# eBox_Power.net
KiCad netlist of a schematic drawn in Altium Designer
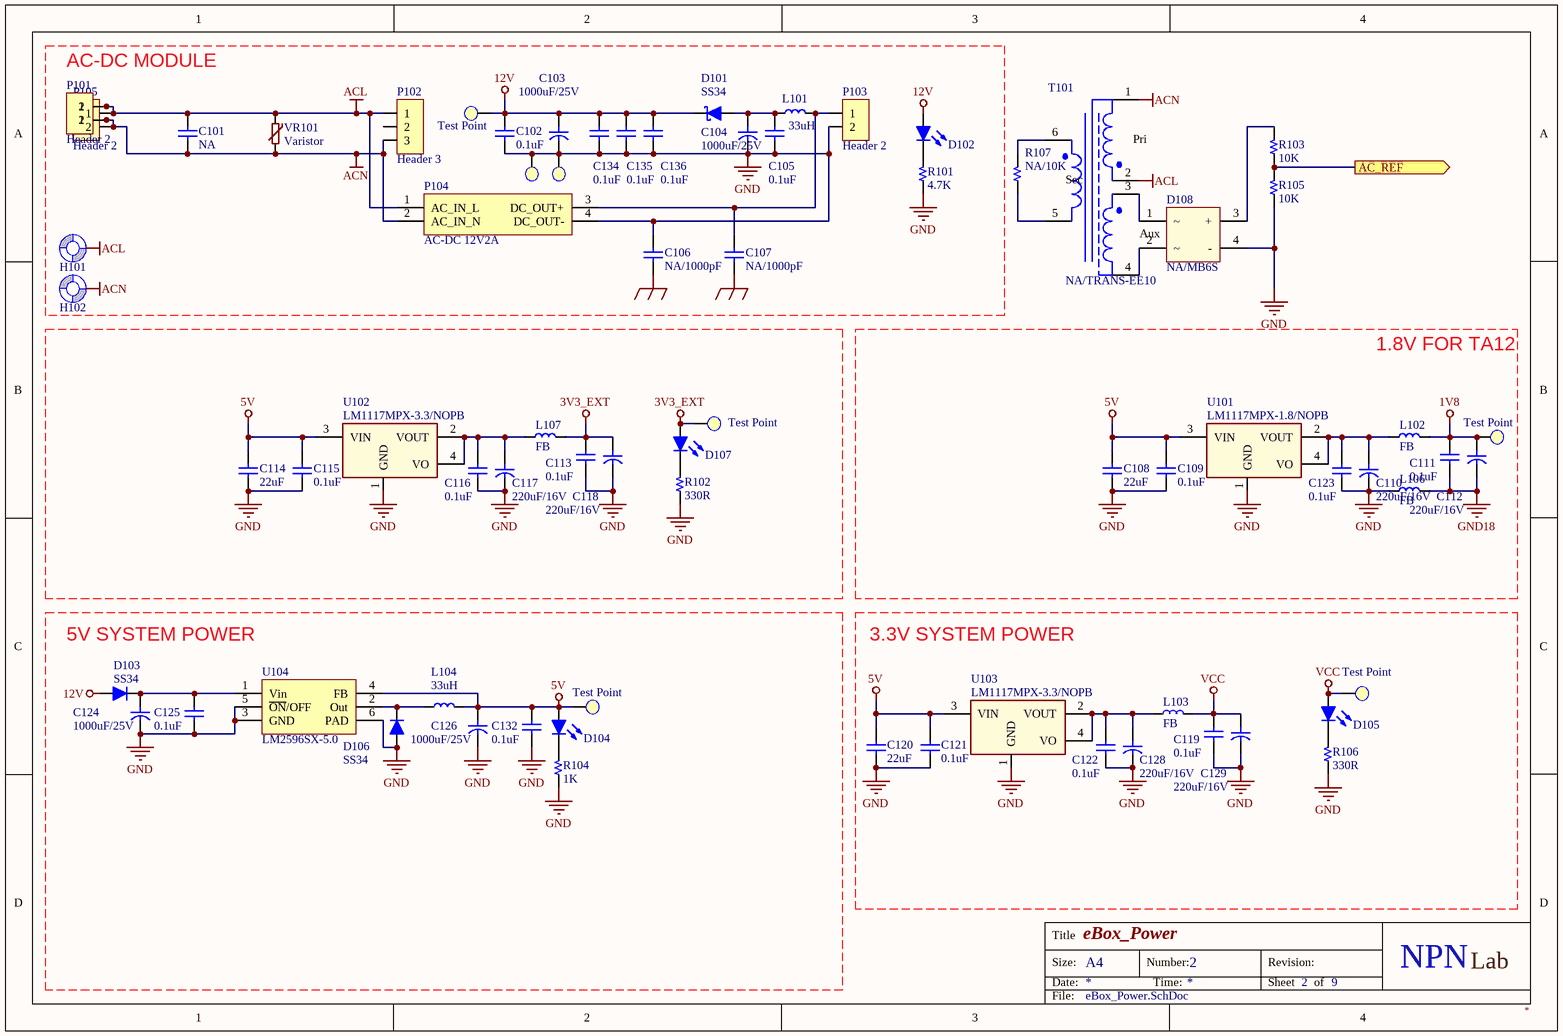
[diagram p0: eBox_Power.SchDoc]

(export (version "E")
  (design (tool "Eeschema 10.0.6"))
  (components
    (comp (ref "1V8")
      (value "Test Point")
      (footprint "TestPoint/SMD/1.5mm")
      (libsource (lib "chipfc_altium_libs_extras") (part "Test Point"))
    )
    (comp (ref "3V3EXT")
      (value "Test Point")
      (footprint "TestPoint/SMD/1.5mm")
      (libsource (lib "chipfc_altium_libs_extras") (part "Test Point"))
    )
    (comp (ref "5V")
      (value "Test Point")
      (footprint "TestPoint/SMD/1.5mm")
      (libsource (lib "chipfc_altium_libs_extras") (part "Test Point"))
    )
    (comp (ref "12V")
      (value "Test Point")
      (footprint "TestPoint/SMD/1.5mm")
      (libsource (lib "chipfc_altium_libs_extras") (part "Test Point"))
    )
    (comp (ref "C101")
      (value "NA")
      (footprint "CAP Ceramic/D7.0/F7.5")
      (description "Capacitor non-pol")
      (libsource (lib "chipfc_altium_libs") (part "Capacitor NP"))
    )
    (comp (ref "C102")
      (value "0.1uF")
      (footprint "C 0805")
      (description "CAP CER 0.1UF 50V X7R 0805")
      (libsource (lib "chipfc_altium_libs") (part "Capacitor NP"))
    )
    (comp (ref "C103")
      (value "1000uF/25V")
      (footprint "CAP/D100/H200/LS50")
      (description "CAP ALUM 1000UF 20% 25V RADIAL")
      (libsource (lib "chipfc_altium_libs") (part "Capacitor"))
    )
    (comp (ref "C104")
      (value "1000uF/25V")
      (footprint "CAP/D100/H200/LS50")
      (description "CAP ALUM 1000UF 20% 25V RADIAL")
      (libsource (lib "chipfc_altium_libs") (part "Capacitor"))
    )
    (comp (ref "C105")
      (value "0.1uF")
      (footprint "C 0805")
      (description "CAP CER 0.1UF 50V X7R 0805")
      (libsource (lib "chipfc_altium_libs") (part "Capacitor NP"))
    )
    (comp (ref "C106")
      (value "NA/1000pF")
      (footprint "CAP Ceramic/W300")
      (description "Capacitor non-pol")
      (libsource (lib "chipfc_altium_libs") (part "Capacitor NP"))
    )
    (comp (ref "C107")
      (value "NA/1000pF")
      (footprint "CAP Ceramic/W300")
      (description "Capacitor non-pol")
      (libsource (lib "chipfc_altium_libs") (part "Capacitor NP"))
    )
    (comp (ref "C108")
      (value "22uF")
      (footprint "C 1210 mix 0805")
      (description "CAP CER 22UF 10% 16V X7R 1210")
      (libsource (lib "chipfc_altium_libs") (part "Capacitor NP"))
    )
    (comp (ref "C109")
      (value "0.1uF")
      (footprint "C 0805")
      (description "CAP CER 0.1UF 50V X7R 0805")
      (libsource (lib "chipfc_altium_libs") (part "Capacitor NP"))
    )
    (comp (ref "C110")
      (value "220uF/16V")
      (footprint "CYL/D.250/LS.100-D63H70P25")
      (description "CAP ALUM 220UF 20% 16V RADIAL")
      (libsource (lib "") (part "Capacitor_1"))
    )
    (comp (ref "C111")
      (value "0.1uF")
      (footprint "C 0805")
      (description "CAP CER 0.1UF 50V X7R 0805")
      (libsource (lib "chipfc_altium_libs") (part "Capacitor NP"))
    )
    (comp (ref "C112")
      (value "220uF/16V")
      (footprint "CYL/D.250/LS.100-D63H70P25")
      (description "CAP ALUM 220UF 20% 16V RADIAL")
      (libsource (lib "") (part "Capacitor_1"))
    )
    (comp (ref "C113")
      (value "0.1uF")
      (footprint "C 0805")
      (description "CAP CER 0.1UF 50V X7R 0805")
      (libsource (lib "chipfc_altium_libs") (part "Capacitor NP"))
    )
    (comp (ref "C114")
      (value "22uF")
      (footprint "C 1210 mix 0805")
      (description "CAP CER 22UF 10% 16V X7R 1210")
      (libsource (lib "chipfc_altium_libs") (part "Capacitor NP"))
    )
    (comp (ref "C115")
      (value "0.1uF")
      (footprint "C 0805")
      (description "CAP CER 0.1UF 50V X7R 0805")
      (libsource (lib "chipfc_altium_libs") (part "Capacitor NP"))
    )
    (comp (ref "C116")
      (value "0.1uF")
      (footprint "C 0805")
      (description "CAP CER 0.1UF 50V X7R 0805")
      (libsource (lib "chipfc_altium_libs") (part "Capacitor NP"))
    )
    (comp (ref "C117")
      (value "220uF/16V")
      (footprint "CYL/D.250/LS.100-D63H70P25")
      (description "CAP ALUM 220UF 20% 16V RADIAL")
      (libsource (lib "") (part "Capacitor_1"))
    )
    (comp (ref "C118")
      (value "220uF/16V")
      (footprint "CYL/D.250/LS.100-D63H70P25")
      (description "CAP ALUM 220UF 20% 16V RADIAL")
      (libsource (lib "") (part "Capacitor_1"))
    )
    (comp (ref "C119")
      (value "0.1uF")
      (footprint "C 0805")
      (description "CAP CER 0.1UF 50V X7R 0805")
      (libsource (lib "chipfc_altium_libs") (part "Capacitor NP"))
    )
    (comp (ref "C120")
      (value "22uF")
      (footprint "C 1210 mix 0805")
      (description "CAP CER 22UF 10% 16V X7R 1210")
      (libsource (lib "chipfc_altium_libs") (part "Capacitor NP"))
    )
    (comp (ref "C121")
      (value "0.1uF")
      (footprint "C 0805")
      (description "CAP CER 0.1UF 50V X7R 0805")
      (libsource (lib "chipfc_altium_libs") (part "Capacitor NP"))
    )
    (comp (ref "C122")
      (value "0.1uF")
      (footprint "C 0805")
      (description "CAP CER 0.1UF 50V X7R 0805")
      (libsource (lib "chipfc_altium_libs") (part "Capacitor NP"))
    )
    (comp (ref "C123")
      (value "0.1uF")
      (footprint "C 0805")
      (description "CAP CER 0.1UF 50V X7R 0805")
      (libsource (lib "chipfc_altium_libs") (part "Capacitor NP"))
    )
    (comp (ref "C124")
      (value "1000uF/25V")
      (footprint "CAP/D100/H200/LS50")
      (description "CAP ALUM 1000UF 20% 25V RADIAL")
      (libsource (lib "chipfc_altium_libs") (part "Capacitor"))
    )
    (comp (ref "C125")
      (value "0.1uF")
      (footprint "C 0805")
      (description "CAP CER 0.1UF 50V X7R 0805")
      (libsource (lib "chipfc_altium_libs") (part "Capacitor NP"))
    )
    (comp (ref "C126")
      (value "1000uF/25V")
      (footprint "CAP/D100/H200/LS50")
      (description "CAP ALUM 1000UF 20% 25V RADIAL")
      (libsource (lib "chipfc_altium_libs") (part "Capacitor"))
    )
    (comp (ref "C128")
      (value "220uF/16V")
      (footprint "CYL/D.250/LS.100-D63H70P25")
      (description "CAP ALUM 220UF 20% 16V RADIAL")
      (libsource (lib "") (part "Capacitor_1"))
    )
    (comp (ref "C129")
      (value "220uF/16V")
      (footprint "CYL/D.250/LS.100-D63H70P25")
      (description "CAP ALUM 220UF 20% 16V RADIAL")
      (libsource (lib "") (part "Capacitor_1"))
    )
    (comp (ref "C132")
      (value "0.1uF")
      (footprint "C 0805")
      (description "CAP CER 0.1UF 50V X7R 0805")
      (libsource (lib "chipfc_altium_libs") (part "Capacitor NP"))
    )
    (comp (ref "C134")
      (value "0.1uF")
      (footprint "C 0805")
      (description "CAP CER 0.1UF 50V X7R 0805")
      (libsource (lib "chipfc_altium_libs") (part "Capacitor NP"))
    )
    (comp (ref "C135")
      (value "0.1uF")
      (footprint "C 0805")
      (description "CAP CER 0.1UF 50V X7R 0805")
      (libsource (lib "chipfc_altium_libs") (part "Capacitor NP"))
    )
    (comp (ref "C136")
      (value "0.1uF")
      (footprint "C 0805")
      (description "CAP CER 0.1UF 50V X7R 0805")
      (libsource (lib "chipfc_altium_libs") (part "Capacitor NP"))
    )
    (comp (ref "D101")
      (value "SS34")
      (footprint "DO-214AB (SMC)")
      (description "DIODE SCHOTTKY 40V 3A SUB SMA")
      (libsource (lib "chipfc_altium_libs") (part "Diode Schottky"))
    )
    (comp (ref "D102")
      (value "LED RED 3MM")
      (footprint "LED 3MM - red")
      (description "LED RED DIFFUSED 3MM ROUND T/H")
      (libsource (lib "chipfc_altium_libs") (part "Led"))
    )
    (comp (ref "D103")
      (value "SS34")
      (footprint "DO-214AC (SMA) L")
      (description "DIODE SCHOTTKY 40V 3A SUB SMA")
      (libsource (lib "chipfc_altium_libs") (part "Diode"))
    )
    (comp (ref "D104")
      (value "LED RED 3MM")
      (footprint "LED 3MM - red")
      (description "LED RED DIFFUSED 3MM ROUND T/H")
      (libsource (lib "chipfc_altium_libs") (part "Led"))
    )
    (comp (ref "D105")
      (value "LED RED 3MM")
      (footprint "LED 3MM - red")
      (description "LED RED DIFFUSED 3MM ROUND T/H")
      (libsource (lib "chipfc_altium_libs") (part "Led"))
    )
    (comp (ref "D106")
      (value "SS34")
      (footprint "DO-214AC (SMA) L")
      (description "DIODE SCHOTTKY 40V 3A SUB SMA")
      (libsource (lib "chipfc_altium_libs") (part "Diode"))
    )
    (comp (ref "D107")
      (value "LED RED 3MM")
      (footprint "LED 3MM - red")
      (description "LED RED DIFFUSED 3MM ROUND T/H")
      (libsource (lib "chipfc_altium_libs") (part "Led"))
    )
    (comp (ref "D108")
      (value "NA/MB6S")
      (footprint "DiodeBridge-SOIC4")
      (description "BRIDGE RECT 1P 600V 500MA 4SOIC")
      (fields (field (name "PART NO") "MB6S"))
      (libsource (lib "chipfc_altium_libs") (part "DIODE BRIDGE"))
    )
    (comp (ref "GND2")
      (value "Test Point")
      (footprint "TESTPOINT/1/Black")
      (libsource (lib "chipfc_altium_libs_extras") (part "Test Point"))
    )
    (comp (ref "GND3")
      (value "Test Point")
      (footprint "TESTPOINT/1/Black")
      (libsource (lib "chipfc_altium_libs_extras") (part "Test Point"))
    )
    (comp (ref "H101")
      (value "Screw Hole")
      (footprint "SCREW/3.0/6.0")
      (libsource (lib "chipfc_altium_libs") (part "Screw Hole"))
    )
    (comp (ref "H102")
      (value "Screw Hole")
      (footprint "SCREW/3.0/6.0")
      (libsource (lib "chipfc_altium_libs") (part "Screw Hole"))
    )
    (comp (ref "L101")
      (value "33uH")
      (footprint "Inductor SMD 6.5x6.5x3.0")
      (description "FIXED IND 33UH 3A 105 MOHM SMD")
      (libsource (lib "chipfc_altium_libs") (part "Inductor"))
    )
    (comp (ref "L102")
      (value "FB")
      (footprint "L 0805 (2012)")
      (description "Chip Ferrite Bead")
      (libsource (lib "chipfc_altium_libs") (part "Inductor"))
    )
    (comp (ref "L103")
      (value "FB")
      (footprint "L 0805 (2012)")
      (description "Chip Ferrite Bead")
      (libsource (lib "chipfc_altium_libs") (part "Inductor"))
    )
    (comp (ref "L104")
      (value "33uH")
      (footprint "Inductor SMD 12x12x8")
      (description "FIXED IND 33UH 3A 64.8 MOHM SMD")
      (libsource (lib "chipfc_altium_libs") (part "Inductor"))
    )
    (comp (ref "L105")
      (value "33uH")
      (footprint "Inductor SMD 12x12x8")
      (description "FIXED IND 33UH 3A 64.8 MOHM SMD")
      (libsource (lib "chipfc_altium_libs") (part "Inductor"))
    )
    (comp (ref "L106")
      (value "FB")
      (footprint "L 0805 (2012)")
      (description "Chip Ferrite Bead")
      (libsource (lib "chipfc_altium_libs") (part "Inductor"))
    )
    (comp (ref "L107")
      (value "FB")
      (footprint "L 0805 (2012)")
      (description "Chip Ferrite Bead")
      (libsource (lib "chipfc_altium_libs") (part "Inductor"))
    )
    (comp (ref "P101")
      (value "Header 2")
      (footprint "HDR/Terminal/2/KF55C-10")
      (description "Header, 2-Pin")
      (libsource (lib "") (part "Header 2_1"))
    )
    (comp (ref "P102")
      (value "Header 3")
      (footprint "HDR/Header/3/VH")
      (description "Header, 3-Pin")
      (libsource (lib "chipfc_altium_libs") (part "Header 3"))
    )
    (comp (ref "P103")
      (value "Header 2")
      (footprint "HDR/Header/2/VH")
      (description "Header, 2-Pin")
      (libsource (lib "chipfc_altium_libs") (part "Header 2"))
    )
    (comp (ref "P104")
      (value "AC-DC 12V2A")
      (footprint "AC-DC 12V2A")
      (description "AC-DC 12V2A MODULE")
      (libsource (lib "chipfc_altium_libs") (part "AC-DC 12V3A"))
    )
    (comp (ref "P105")
      (value "Header 2")
      (footprint "HDR/Terminal/2/KF1000")
      (description "Header, 2-Pin")
      (libsource (lib "") (part "Header 2_1"))
    )
    (comp (ref "P106")
      (value "Header 2")
      (footprint "HDR/Terminal/2/KF1000")
      (description "Header, 2-Pin")
      (libsource (lib "") (part "Header 2_2"))
    )
    (comp (ref "R101")
      (value "4.7K")
      (footprint "R 0603")
      (description "RES SMD 4.7K OHM 1% 1/10W 0603")
      (libsource (lib "chipfc_altium_libs") (part "Resistor"))
    )
    (comp (ref "R102")
      (value "330R")
      (footprint "R 0603")
      (description "RES SMD 330 OHM 1% 1/10W 0603")
      (libsource (lib "chipfc_altium_libs") (part "Resistor"))
    )
    (comp (ref "R103")
      (value "10K")
      (footprint "R 0805")
      (description "RES SMD 10K OHM 1% 1/8W 0805")
      (libsource (lib "chipfc_altium_libs") (part "Resistor"))
    )
    (comp (ref "R104")
      (value "1K")
      (footprint "R 0603")
      (description "RES SMD 1K OHM 1% 1/10W 0603")
      (libsource (lib "chipfc_altium_libs") (part "Resistor"))
    )
    (comp (ref "R105")
      (value "10K")
      (footprint "R 0805")
      (description "RES SMD 10K OHM 1% 1/8W 0805")
      (libsource (lib "chipfc_altium_libs") (part "Resistor"))
    )
    (comp (ref "R106")
      (value "330R")
      (footprint "R 0603")
      (description "RES SMD 330 OHM 1% 1/10W 0603")
      (libsource (lib "chipfc_altium_libs") (part "Resistor"))
    )
    (comp (ref "R107")
      (value "NA/10K")
      (footprint "R 0805")
      (description "RES SMD 10K OHM 5% 1/8W 0805")
      (libsource (lib "chipfc_altium_libs") (part "Resistor"))
    )
    (comp (ref "T101")
      (value "NA/TRANS-EE10")
      (footprint "Trans. EE10/6P/F")
      (description "Transformer 6-PIN")
      (libsource (lib "chipfc_altium_libs") (part "Trans 6-PIN"))
    )
    (comp (ref "U101")
      (value "LM1117MPX-1.8/NOPB")
      (footprint "SOT-223")
      (description "IC REG LINEAR 1.8V 800MA SOT223")
      (libsource (lib "chipfc_altium_libs") (part "AMS1117"))
    )
    (comp (ref "U102")
      (value "LM1117MPX-3.3/NOPB")
      (footprint "SOT-223")
      (description "IC REG LINEAR 3.3V 800MA SOT223")
      (libsource (lib "chipfc_altium_libs") (part "AMS1117"))
    )
    (comp (ref "U103")
      (value "LM1117MPX-3.3/NOPB")
      (footprint "SOT-223")
      (description "IC REG LINEAR 3.3V 800MA SOT223")
      (libsource (lib "chipfc_altium_libs") (part "AMS1117"))
    )
    (comp (ref "U104")
      (value "LM2596SX-5.0")
      (footprint "TO-263-6")
      (description "IC REG BUCK 5V 3A TO263-5")
      (fields (field (name "PART NO") "LM2576SX-5.0/NOPB"))
      (libsource (lib "chipfc_altium_libs") (part "LM2576SX-5.0"))
    )
    (comp (ref "VCC")
      (value "Test Point")
      (footprint "TestPoint/SMD/1.5mm")
      (libsource (lib "chipfc_altium_libs_extras") (part "Test Point"))
    )
    (comp (ref "VR101")
      (value "Varistor")
      (footprint "VARISTOR DISC 5MM/7MM")
      (libsource (lib "chipfc_altium_libs") (part "Varistor"))
    )
  )
  (nets
    (net (code "1") (name "/AC_REF") (class "Default")
      (node (ref "R103") (pin "1") (pinfunction "1_1") (pintype "passive"))
      (node (ref "R105") (pin "2") (pinfunction "2_2") (pintype "passive"))
    )
    (net (code "2") (name "1V8") (class "Default")
      (node (ref "1V8") (pin "1") (pinfunction "TP_1") (pintype "passive"))
      (node (ref "C111") (pin "1") (pinfunction "1_1") (pintype "passive"))
      (node (ref "C112") (pin "1") (pinfunction "1_1") (pintype "passive"))
      (node (ref "L102") (pin "2") (pinfunction "2_2") (pintype "passive"))
    )
    (net (code "3") (name "3V3_EXT") (class "Default")
      (node (ref "3V3EXT") (pin "1") (pinfunction "TP_1") (pintype "passive"))
      (node (ref "C113") (pin "1") (pinfunction "1_1") (pintype "passive"))
      (node (ref "C118") (pin "1") (pinfunction "1_1") (pintype "passive"))
      (node (ref "D107") (pin "1") (pinfunction "A_1") (pintype "passive"))
      (node (ref "L107") (pin "2") (pinfunction "2_2") (pintype "passive"))
    )
    (net (code "4") (name "5V") (class "Default")
      (node (ref "5V") (pin "1") (pinfunction "TP_1") (pintype "passive"))
      (node (ref "C108") (pin "1") (pinfunction "1_1") (pintype "passive"))
      (node (ref "C109") (pin "1") (pinfunction "1_1") (pintype "passive"))
      (node (ref "C114") (pin "1") (pinfunction "1_1") (pintype "passive"))
      (node (ref "C115") (pin "1") (pinfunction "1_1") (pintype "passive"))
      (node (ref "C120") (pin "1") (pinfunction "1_1") (pintype "passive"))
      (node (ref "C121") (pin "1") (pinfunction "1_1") (pintype "passive"))
      (node (ref "C126") (pin "1") (pinfunction "1_1") (pintype "passive"))
      (node (ref "C132") (pin "1") (pinfunction "1_1") (pintype "passive"))
      (node (ref "D104") (pin "1") (pinfunction "A_1") (pintype "passive"))
      (node (ref "L104") (pin "2") (pinfunction "2_2") (pintype "passive"))
      (node (ref "U101") (pin "3") (pinfunction "VIN_3") (pintype "power_in"))
      (node (ref "U102") (pin "3") (pinfunction "VIN_3") (pintype "power_in"))
      (node (ref "U103") (pin "3") (pinfunction "VIN_3") (pintype "power_in"))
      (node (ref "U104") (pin "4") (pinfunction "FB_4") (pintype "passive"))
    )
    (net (code "5") (name "12V") (class "Default")
      (node (ref "12V") (pin "1") (pinfunction "TP_1") (pintype "passive"))
      (node (ref "C102") (pin "1") (pinfunction "1_1") (pintype "passive"))
      (node (ref "C103") (pin "1") (pinfunction "1_1") (pintype "passive"))
      (node (ref "C134") (pin "1") (pinfunction "1_1") (pintype "passive"))
      (node (ref "C135") (pin "1") (pinfunction "1_1") (pintype "passive"))
      (node (ref "C136") (pin "1") (pinfunction "1_1") (pintype "passive"))
      (node (ref "D101") (pin "2") (pinfunction "K_2") (pintype "passive"))
      (node (ref "D102") (pin "1") (pinfunction "A_1") (pintype "passive"))
      (node (ref "D103") (pin "1") (pinfunction "A_1") (pintype "passive"))
    )
    (net (code "6") (name "ACL") (class "Default")
      (node (ref "C101") (pin "1") (pinfunction "1_1") (pintype "passive"))
      (node (ref "H101") (pin "1") (pinfunction "Screw_1") (pintype "passive"))
      (node (ref "P101") (pin "1") (pinfunction "1_1") (pintype "passive"))
      (node (ref "P102") (pin "1") (pinfunction "1_1") (pintype "passive"))
      (node (ref "P104") (pin "1") (pinfunction "AC_IN_L_1") (pintype "passive"))
      (node (ref "P105") (pin "1") (pinfunction "1_1") (pintype "passive"))
      (node (ref "P106") (pin "2") (pinfunction "2_2") (pintype "passive"))
      (node (ref "T101") (pin "2") (pinfunction "A2_2") (pintype "passive"))
      (node (ref "VR101") (pin "2") (pinfunction "2_2") (pintype "passive"))
    )
    (net (code "7") (name "ACN") (class "Default")
      (node (ref "C101") (pin "2") (pinfunction "2_2") (pintype "passive"))
      (node (ref "H102") (pin "1") (pinfunction "Screw_1") (pintype "passive"))
      (node (ref "P101") (pin "2") (pinfunction "2_2") (pintype "passive"))
      (node (ref "P102") (pin "3") (pinfunction "3_3") (pintype "passive"))
      (node (ref "P104") (pin "2") (pinfunction "AC_IN_N_2") (pintype "passive"))
      (node (ref "P105") (pin "2") (pinfunction "2_2") (pintype "passive"))
      (node (ref "P106") (pin "1") (pinfunction "1_1") (pintype "passive"))
      (node (ref "T101") (pin "1") (pinfunction "A1_1") (pintype "passive"))
      (node (ref "VR101") (pin "1") (pinfunction "1_1") (pintype "passive"))
    )
    (net (code "8") (name "GND") (class "Default")
      (node (ref "C102") (pin "2") (pinfunction "2_2") (pintype "passive"))
      (node (ref "C103") (pin "2") (pinfunction "2_2") (pintype "passive"))
      (node (ref "C104") (pin "2") (pinfunction "2_2") (pintype "passive"))
      (node (ref "C105") (pin "2") (pinfunction "2_2") (pintype "passive"))
      (node (ref "C106") (pin "1") (pinfunction "1_1") (pintype "passive"))
      (node (ref "C108") (pin "2") (pinfunction "2_2") (pintype "passive"))
      (node (ref "C109") (pin "2") (pinfunction "2_2") (pintype "passive"))
      (node (ref "C110") (pin "2") (pinfunction "2_2") (pintype "passive"))
      (node (ref "C113") (pin "2") (pinfunction "2_2") (pintype "passive"))
      (node (ref "C114") (pin "2") (pinfunction "2_2") (pintype "passive"))
      (node (ref "C115") (pin "2") (pinfunction "2_2") (pintype "passive"))
      (node (ref "C116") (pin "2") (pinfunction "2_2") (pintype "passive"))
      (node (ref "C117") (pin "2") (pinfunction "2_2") (pintype "passive"))
      (node (ref "C118") (pin "2") (pinfunction "2_2") (pintype "passive"))
      (node (ref "C119") (pin "2") (pinfunction "2_2") (pintype "passive"))
      (node (ref "C120") (pin "2") (pinfunction "2_2") (pintype "passive"))
      (node (ref "C121") (pin "2") (pinfunction "2_2") (pintype "passive"))
      (node (ref "C122") (pin "2") (pinfunction "2_2") (pintype "passive"))
      (node (ref "C123") (pin "2") (pinfunction "2_2") (pintype "passive"))
      (node (ref "C124") (pin "2") (pinfunction "2_2") (pintype "passive"))
      (node (ref "C125") (pin "2") (pinfunction "2_2") (pintype "passive"))
      (node (ref "C126") (pin "2") (pinfunction "2_2") (pintype "passive"))
      (node (ref "C128") (pin "2") (pinfunction "2_2") (pintype "passive"))
      (node (ref "C129") (pin "2") (pinfunction "2_2") (pintype "passive"))
      (node (ref "C132") (pin "2") (pinfunction "2_2") (pintype "passive"))
      (node (ref "C134") (pin "2") (pinfunction "2_2") (pintype "passive"))
      (node (ref "C135") (pin "2") (pinfunction "2_2") (pintype "passive"))
      (node (ref "C136") (pin "2") (pinfunction "2_2") (pintype "passive"))
      (node (ref "D106") (pin "1") (pinfunction "A_1") (pintype "passive"))
      (node (ref "D108") (pin "4") (pinfunction "-_4") (pintype "passive"))
      (node (ref "GND2") (pin "1") (pinfunction "TP_1") (pintype "passive"))
      (node (ref "GND3") (pin "1") (pinfunction "TP_1") (pintype "passive"))
      (node (ref "L106") (pin "1") (pinfunction "1_1") (pintype "passive"))
      (node (ref "P103") (pin "2") (pinfunction "2_2") (pintype "passive"))
      (node (ref "P104") (pin "4") (pinfunction "DC_OUT-_4") (pintype "passive"))
      (node (ref "R101") (pin "1") (pinfunction "1_1") (pintype "passive"))
      (node (ref "R102") (pin "1") (pinfunction "1_1") (pintype "passive"))
      (node (ref "R104") (pin "1") (pinfunction "1_1") (pintype "passive"))
      (node (ref "R105") (pin "1") (pinfunction "1_1") (pintype "passive"))
      (node (ref "R106") (pin "1") (pinfunction "1_1") (pintype "passive"))
      (node (ref "U101") (pin "1") (pinfunction "GND_1") (pintype "passive"))
      (node (ref "U102") (pin "1") (pinfunction "GND_1") (pintype "passive"))
      (node (ref "U103") (pin "1") (pinfunction "GND_1") (pintype "passive"))
      (node (ref "U104") (pin "3") (pinfunction "GND_3") (pintype "passive"))
      (node (ref "U104") (pin "5") (pinfunction "~{ON}/OFF_5") (pintype "passive"))
      (node (ref "U104") (pin "6") (pinfunction "PAD_6") (pintype "passive"))
    )
    (net (code "9") (name "GND18") (class "Default")
      (node (ref "C111") (pin "2") (pinfunction "2_2") (pintype "passive"))
      (node (ref "C112") (pin "2") (pinfunction "2_2") (pintype "passive"))
      (node (ref "L106") (pin "2") (pinfunction "2_2") (pintype "passive"))
    )
    (net (code "10") (name "GNDEARTH") (class "Default")
      (node (ref "C106") (pin "2") (pinfunction "2_2") (pintype "passive"))
      (node (ref "C107") (pin "2") (pinfunction "2_2") (pintype "passive"))
    )
    (net (code "11") (name "Net-(D101-A)") (class "Default")
      (node (ref "C104") (pin "1") (pinfunction "1_1") (pintype "passive"))
      (node (ref "C105") (pin "1") (pinfunction "1_1") (pintype "passive"))
      (node (ref "D101") (pin "1") (pinfunction "A_1") (pintype "passive"))
      (node (ref "L101") (pin "1") (pinfunction "1_1") (pintype "passive"))
      (node (ref "L105") (pin "1") (pinfunction "1_1") (pintype "passive"))
    )
    (net (code "12") (name "Net-(D102-K)") (class "Default")
      (node (ref "D102") (pin "2") (pinfunction "K_2") (pintype "passive"))
      (node (ref "R101") (pin "2") (pinfunction "2_2") (pintype "passive"))
    )
    (net (code "13") (name "Net-(D103-K)") (class "Default")
      (node (ref "C124") (pin "1") (pinfunction "1_1") (pintype "passive"))
      (node (ref "C125") (pin "1") (pinfunction "1_1") (pintype "passive"))
      (node (ref "D103") (pin "2") (pinfunction "K_2") (pintype "passive"))
      (node (ref "U104") (pin "1") (pinfunction "Vin_1") (pintype "passive"))
    )
    (net (code "14") (name "Net-(D104-K)") (class "Default")
      (node (ref "D104") (pin "2") (pinfunction "K_2") (pintype "passive"))
      (node (ref "R104") (pin "2") (pinfunction "2_2") (pintype "passive"))
    )
    (net (code "15") (name "Net-(D105-K)") (class "Default")
      (node (ref "D105") (pin "2") (pinfunction "K_2") (pintype "passive"))
      (node (ref "R106") (pin "2") (pinfunction "2_2") (pintype "passive"))
    )
    (net (code "16") (name "Net-(D106-K)") (class "Default")
      (node (ref "D106") (pin "2") (pinfunction "K_2") (pintype "passive"))
      (node (ref "L104") (pin "1") (pinfunction "1_1") (pintype "passive"))
      (node (ref "U104") (pin "2") (pinfunction "Out_2") (pintype "passive"))
    )
    (net (code "17") (name "Net-(D107-K)") (class "Default")
      (node (ref "D107") (pin "2") (pinfunction "K_2") (pintype "passive"))
      (node (ref "R102") (pin "2") (pinfunction "2_2") (pintype "passive"))
    )
    (net (code "18") (name "Net-(D108-+)") (class "Default")
      (node (ref "D108") (pin "3") (pinfunction "+_3") (pintype "passive"))
      (node (ref "R103") (pin "2") (pinfunction "2_2") (pintype "passive"))
    )
    (net (code "19") (name "Net-(P104-DC_OUT+)") (class "Default")
      (node (ref "C107") (pin "1") (pinfunction "1_1") (pintype "passive"))
      (node (ref "L101") (pin "2") (pinfunction "2_2") (pintype "passive"))
      (node (ref "L105") (pin "2") (pinfunction "2_2") (pintype "passive"))
      (node (ref "P103") (pin "1") (pinfunction "1_1") (pintype "passive"))
      (node (ref "P104") (pin "3") (pinfunction "DC_OUT+_3") (pintype "passive"))
    )
    (net (code "20") (name "Net-(T101-B1)") (class "Default")
      (node (ref "D108") (pin "1") (pinfunction "~_1") (pintype "passive"))
      (node (ref "T101") (pin "3") (pinfunction "B1_3") (pintype "passive"))
    )
    (net (code "21") (name "Net-(T101-B2)") (class "Default")
      (node (ref "D108") (pin "2") (pinfunction "~_2") (pintype "passive"))
      (node (ref "T101") (pin "4") (pinfunction "B2_4") (pintype "passive"))
    )
    (net (code "22") (name "Net-(T101-C1)") (class "Default")
      (node (ref "R107") (pin "2") (pinfunction "2_2") (pintype "passive"))
      (node (ref "T101") (pin "6") (pinfunction "C1_6") (pintype "passive"))
    )
    (net (code "23") (name "Net-(T101-C2)") (class "Default")
      (node (ref "R107") (pin "1") (pinfunction "1_1") (pintype "passive"))
      (node (ref "T101") (pin "5") (pinfunction "C2_5") (pintype "passive"))
    )
    (net (code "24") (name "Net-(U101-VO)") (class "Default")
      (node (ref "C110") (pin "1") (pinfunction "1_1") (pintype "passive"))
      (node (ref "C123") (pin "1") (pinfunction "1_1") (pintype "passive"))
      (node (ref "L102") (pin "1") (pinfunction "1_1") (pintype "passive"))
      (node (ref "U101") (pin "2") (pinfunction "VOUT_2") (pintype "passive"))
      (node (ref "U101") (pin "4") (pinfunction "VO_4") (pintype "passive"))
    )
    (net (code "25") (name "Net-(U102-VO)") (class "Default")
      (node (ref "C116") (pin "1") (pinfunction "1_1") (pintype "passive"))
      (node (ref "C117") (pin "1") (pinfunction "1_1") (pintype "passive"))
      (node (ref "L107") (pin "1") (pinfunction "1_1") (pintype "passive"))
      (node (ref "U102") (pin "2") (pinfunction "VOUT_2") (pintype "passive"))
      (node (ref "U102") (pin "4") (pinfunction "VO_4") (pintype "passive"))
    )
    (net (code "26") (name "Net-(U103-VO)") (class "Default")
      (node (ref "C122") (pin "1") (pinfunction "1_1") (pintype "passive"))
      (node (ref "C128") (pin "1") (pinfunction "1_1") (pintype "passive"))
      (node (ref "L103") (pin "1") (pinfunction "1_1") (pintype "passive"))
      (node (ref "U103") (pin "2") (pinfunction "VOUT_2") (pintype "passive"))
      (node (ref "U103") (pin "4") (pinfunction "VO_4") (pintype "passive"))
    )
    (net (code "27") (name "VCC") (class "Default")
      (node (ref "C119") (pin "1") (pinfunction "1_1") (pintype "passive"))
      (node (ref "C129") (pin "1") (pinfunction "1_1") (pintype "passive"))
      (node (ref "D105") (pin "1") (pinfunction "A_1") (pintype "passive"))
      (node (ref "L103") (pin "2") (pinfunction "2_2") (pintype "passive"))
      (node (ref "VCC") (pin "1") (pinfunction "TP_1") (pintype "passive"))
    )
    (net (code "28") (name "unconnected-(P102-Pad2)") (class "Default")
      (node (ref "P102") (pin "2") (pinfunction "2_2") (pintype "passive"))
    )
  )
)
